# Battery_Gauge_LED_Board.net
KiCad netlist of a schematic drawn in EAGLE
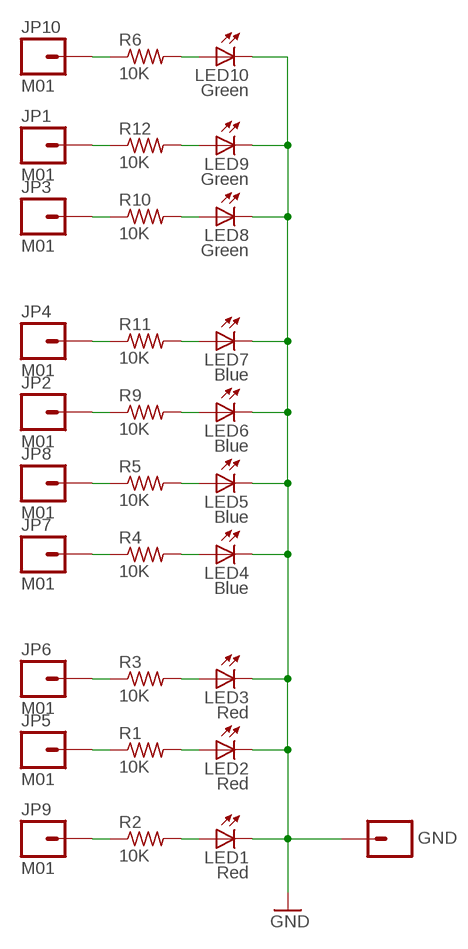
[diagram p0: schematic, sheet 1]

(export (version "E")
  (design (tool "Eeschema 10.0.6"))
  (components
    (comp (ref "GND")
      (value "M01")
      (footprint "eagle-import:1X01_SMD_SM")
      (libsource (lib "eagle-import") (part "M01"))
    )
    (comp (ref "JP1")
      (value "M01")
      (footprint "eagle-import:1X01_SMD_SM")
      (libsource (lib "eagle-import") (part "M01"))
    )
    (comp (ref "JP2")
      (value "M01")
      (footprint "eagle-import:1X01_SMD_SM")
      (libsource (lib "eagle-import") (part "M01"))
    )
    (comp (ref "JP3")
      (value "M01")
      (footprint "eagle-import:1X01_SMD_SM")
      (libsource (lib "eagle-import") (part "M01"))
    )
    (comp (ref "JP4")
      (value "M01")
      (footprint "eagle-import:1X01_SMD_SM")
      (libsource (lib "eagle-import") (part "M01"))
    )
    (comp (ref "JP5")
      (value "M01")
      (footprint "eagle-import:1X01_SMD_SM")
      (libsource (lib "eagle-import") (part "M01"))
    )
    (comp (ref "JP6")
      (value "M01")
      (footprint "eagle-import:1X01_SMD_SM")
      (libsource (lib "eagle-import") (part "M01"))
    )
    (comp (ref "JP7")
      (value "M01")
      (footprint "eagle-import:1X01_SMD_SM")
      (libsource (lib "eagle-import") (part "M01"))
    )
    (comp (ref "JP8")
      (value "M01")
      (footprint "eagle-import:1X01_SMD_SM")
      (libsource (lib "eagle-import") (part "M01"))
    )
    (comp (ref "JP9")
      (value "M01")
      (footprint "eagle-import:1X01_SMD_SM")
      (libsource (lib "eagle-import") (part "M01"))
    )
    (comp (ref "JP10")
      (value "M01")
      (footprint "eagle-import:1X01_SMD_SM")
      (libsource (lib "eagle-import") (part "M01"))
    )
    (comp (ref "LED1")
      (value "Red")
      (footprint "eagle-import:CHIPLED_1206_SLIM")
      (libsource (lib "eagle-import") (part "LED1206_SLIM"))
    )
    (comp (ref "LED2")
      (value "Red")
      (footprint "eagle-import:CHIPLED_1206_SLIM")
      (libsource (lib "eagle-import") (part "LED1206_SLIM"))
    )
    (comp (ref "LED3")
      (value "Red")
      (footprint "eagle-import:CHIPLED_1206_SLIM")
      (libsource (lib "eagle-import") (part "LED1206_SLIM"))
    )
    (comp (ref "LED4")
      (value "Blue")
      (footprint "eagle-import:CHIPLED_1206_SLIM")
      (libsource (lib "eagle-import") (part "LED1206_SLIM"))
    )
    (comp (ref "LED5")
      (value "Blue")
      (footprint "eagle-import:CHIPLED_1206_SLIM")
      (libsource (lib "eagle-import") (part "LED1206_SLIM"))
    )
    (comp (ref "LED6")
      (value "Blue")
      (footprint "eagle-import:CHIPLED_1206_SLIM")
      (libsource (lib "eagle-import") (part "LED1206_SLIM"))
    )
    (comp (ref "LED7")
      (value "Blue")
      (footprint "eagle-import:CHIPLED_1206_SLIM")
      (libsource (lib "eagle-import") (part "LED1206_SLIM"))
    )
    (comp (ref "LED8")
      (value "Green")
      (footprint "eagle-import:CHIPLED_1206_SLIM")
      (libsource (lib "eagle-import") (part "LED1206_SLIM"))
    )
    (comp (ref "LED9")
      (value "Green")
      (footprint "eagle-import:CHIPLED_1206_SLIM")
      (libsource (lib "eagle-import") (part "LED1206_SLIM"))
    )
    (comp (ref "LED10")
      (value "Green")
      (footprint "eagle-import:CHIPLED_1206_SLIM")
      (libsource (lib "eagle-import") (part "LED1206_SLIM"))
    )
    (comp (ref "R1")
      (value "10K")
      (footprint "eagle-import:R0805_2")
      (libsource (lib "eagle-import") (part "R-US_R0805_2"))
    )
    (comp (ref "R2")
      (value "10K")
      (footprint "eagle-import:R0805_2")
      (libsource (lib "eagle-import") (part "R-US_R0805_2"))
    )
    (comp (ref "R3")
      (value "10K")
      (footprint "eagle-import:R0805_2")
      (libsource (lib "eagle-import") (part "R-US_R0805_2"))
    )
    (comp (ref "R4")
      (value "10K")
      (footprint "eagle-import:R0805_2")
      (libsource (lib "eagle-import") (part "R-US_R0805_2"))
    )
    (comp (ref "R5")
      (value "10K")
      (footprint "eagle-import:R0805_2")
      (libsource (lib "eagle-import") (part "R-US_R0805_2"))
    )
    (comp (ref "R6")
      (value "10K")
      (footprint "eagle-import:R0805_2")
      (libsource (lib "eagle-import") (part "R-US_R0805_2"))
    )
    (comp (ref "R9")
      (value "10K")
      (footprint "eagle-import:R0805_2")
      (libsource (lib "eagle-import") (part "R-US_R0805_2"))
    )
    (comp (ref "R10")
      (value "10K")
      (footprint "eagle-import:R0805_2")
      (libsource (lib "eagle-import") (part "R-US_R0805_2"))
    )
    (comp (ref "R11")
      (value "10K")
      (footprint "eagle-import:R0805_2")
      (libsource (lib "eagle-import") (part "R-US_R0805_2"))
    )
    (comp (ref "R12")
      (value "10K")
      (footprint "eagle-import:R0805_2")
      (libsource (lib "eagle-import") (part "R-US_R0805_2"))
    )
  )
  (nets
    (net (code "1") (name "GND") (class "Default")
      (node (ref "GND") (pin "P$1") (pinfunction "1_P$1") (pintype "passive"))
      (node (ref "LED1") (pin "C") (pinfunction "C_C") (pintype "passive"))
      (node (ref "LED10") (pin "C") (pinfunction "C_C") (pintype "passive"))
      (node (ref "LED2") (pin "C") (pinfunction "C_C") (pintype "passive"))
      (node (ref "LED3") (pin "C") (pinfunction "C_C") (pintype "passive"))
      (node (ref "LED4") (pin "C") (pinfunction "C_C") (pintype "passive"))
      (node (ref "LED5") (pin "C") (pinfunction "C_C") (pintype "passive"))
      (node (ref "LED6") (pin "C") (pinfunction "C_C") (pintype "passive"))
      (node (ref "LED7") (pin "C") (pinfunction "C_C") (pintype "passive"))
      (node (ref "LED8") (pin "C") (pinfunction "C_C") (pintype "passive"))
      (node (ref "LED9") (pin "C") (pinfunction "C_C") (pintype "passive"))
    )
    (net (code "2") (name "Net-(JP1-1)") (class "Default")
      (node (ref "JP1") (pin "P$1") (pinfunction "1_P$1") (pintype "passive"))
      (node (ref "R12") (pin "1") (pinfunction "1_1") (pintype "passive"))
    )
    (net (code "3") (name "Net-(JP2-1)") (class "Default")
      (node (ref "JP2") (pin "P$1") (pinfunction "1_P$1") (pintype "passive"))
      (node (ref "R9") (pin "1") (pinfunction "1_1") (pintype "passive"))
    )
    (net (code "4") (name "Net-(JP3-1)") (class "Default")
      (node (ref "JP3") (pin "P$1") (pinfunction "1_P$1") (pintype "passive"))
      (node (ref "R10") (pin "1") (pinfunction "1_1") (pintype "passive"))
    )
    (net (code "5") (name "Net-(JP4-1)") (class "Default")
      (node (ref "JP4") (pin "P$1") (pinfunction "1_P$1") (pintype "passive"))
      (node (ref "R11") (pin "1") (pinfunction "1_1") (pintype "passive"))
    )
    (net (code "6") (name "Net-(JP5-1)") (class "Default")
      (node (ref "JP5") (pin "P$1") (pinfunction "1_P$1") (pintype "passive"))
      (node (ref "R1") (pin "1") (pinfunction "1_1") (pintype "passive"))
    )
    (net (code "7") (name "Net-(JP6-1)") (class "Default")
      (node (ref "JP6") (pin "P$1") (pinfunction "1_P$1") (pintype "passive"))
      (node (ref "R3") (pin "1") (pinfunction "1_1") (pintype "passive"))
    )
    (net (code "8") (name "Net-(JP7-1)") (class "Default")
      (node (ref "JP7") (pin "P$1") (pinfunction "1_P$1") (pintype "passive"))
      (node (ref "R4") (pin "1") (pinfunction "1_1") (pintype "passive"))
    )
    (net (code "9") (name "Net-(JP8-1)") (class "Default")
      (node (ref "JP8") (pin "P$1") (pinfunction "1_P$1") (pintype "passive"))
      (node (ref "R5") (pin "1") (pinfunction "1_1") (pintype "passive"))
    )
    (net (code "10") (name "Net-(JP9-1)") (class "Default")
      (node (ref "JP9") (pin "P$1") (pinfunction "1_P$1") (pintype "passive"))
      (node (ref "R2") (pin "1") (pinfunction "1_1") (pintype "passive"))
    )
    (net (code "11") (name "Net-(JP10-1)") (class "Default")
      (node (ref "JP10") (pin "P$1") (pinfunction "1_P$1") (pintype "passive"))
      (node (ref "R6") (pin "1") (pinfunction "1_1") (pintype "passive"))
    )
    (net (code "12") (name "Net-(LED1-PadA)") (class "Default")
      (node (ref "LED1") (pin "A") (pinfunction "A_A") (pintype "passive"))
      (node (ref "R2") (pin "2") (pinfunction "2_2") (pintype "passive"))
    )
    (net (code "13") (name "Net-(LED2-PadA)") (class "Default")
      (node (ref "LED2") (pin "A") (pinfunction "A_A") (pintype "passive"))
      (node (ref "R1") (pin "2") (pinfunction "2_2") (pintype "passive"))
    )
    (net (code "14") (name "Net-(LED3-PadA)") (class "Default")
      (node (ref "LED3") (pin "A") (pinfunction "A_A") (pintype "passive"))
      (node (ref "R3") (pin "2") (pinfunction "2_2") (pintype "passive"))
    )
    (net (code "15") (name "Net-(LED4-PadA)") (class "Default")
      (node (ref "LED4") (pin "A") (pinfunction "A_A") (pintype "passive"))
      (node (ref "R4") (pin "2") (pinfunction "2_2") (pintype "passive"))
    )
    (net (code "16") (name "Net-(LED5-PadA)") (class "Default")
      (node (ref "LED5") (pin "A") (pinfunction "A_A") (pintype "passive"))
      (node (ref "R5") (pin "2") (pinfunction "2_2") (pintype "passive"))
    )
    (net (code "17") (name "Net-(LED6-PadA)") (class "Default")
      (node (ref "LED6") (pin "A") (pinfunction "A_A") (pintype "passive"))
      (node (ref "R9") (pin "2") (pinfunction "2_2") (pintype "passive"))
    )
    (net (code "18") (name "Net-(LED7-PadA)") (class "Default")
      (node (ref "LED7") (pin "A") (pinfunction "A_A") (pintype "passive"))
      (node (ref "R11") (pin "2") (pinfunction "2_2") (pintype "passive"))
    )
    (net (code "19") (name "Net-(LED8-PadA)") (class "Default")
      (node (ref "LED8") (pin "A") (pinfunction "A_A") (pintype "passive"))
      (node (ref "R10") (pin "2") (pinfunction "2_2") (pintype "passive"))
    )
    (net (code "20") (name "Net-(LED9-PadA)") (class "Default")
      (node (ref "LED9") (pin "A") (pinfunction "A_A") (pintype "passive"))
      (node (ref "R12") (pin "2") (pinfunction "2_2") (pintype "passive"))
    )
    (net (code "21") (name "Net-(LED10-PadA)") (class "Default")
      (node (ref "LED10") (pin "A") (pinfunction "A_A") (pintype "passive"))
      (node (ref "R6") (pin "2") (pinfunction "2_2") (pintype "passive"))
    )
  )
)
